# Fibre-Optic-Interface_main.net
KiCad netlist of a schematic drawn in Altium Designer
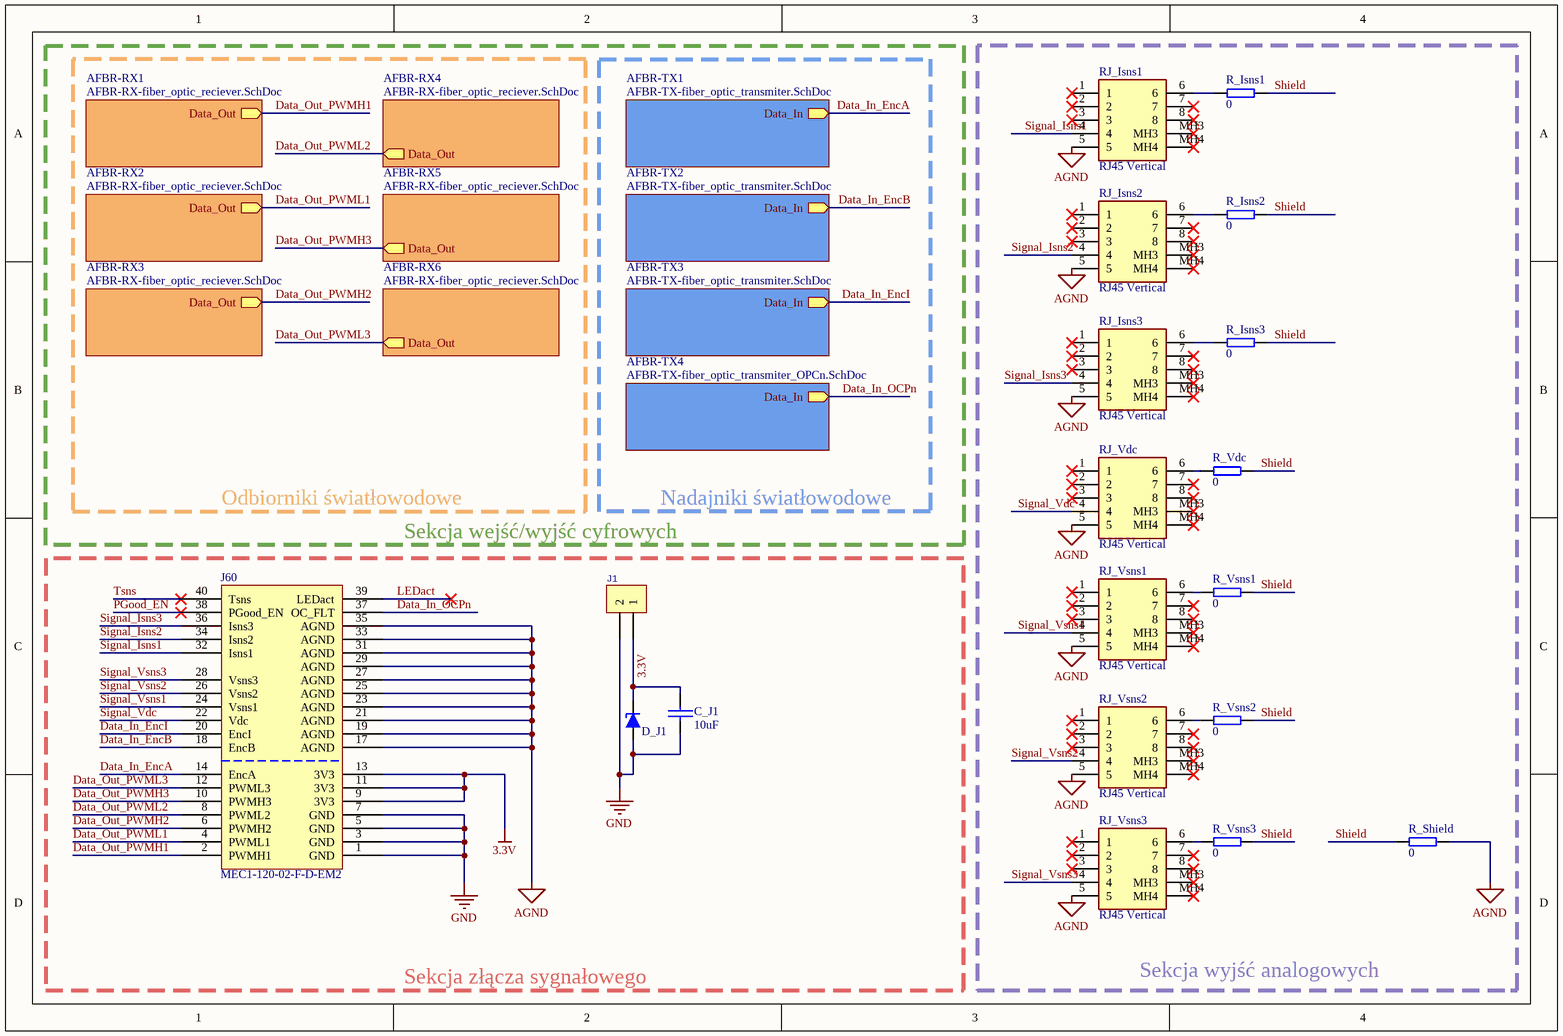
[diagram p0: Fibre-Optic-Interface_main.SchDoc]

(export (version "E")
  (design (tool "Eeschema 10.0.6"))
  (components
    (comp (ref "C_J1")
      (value "10uF")
      (footprint "0603C")
      (description "Capacitor")
      (libsource (lib "PCB_OFC") (part "C_1"))
    )
    (comp (ref "D_J1")
      (value "DIODE_ZENER")
      (footprint "Mini MELF - D")
      (libsource (lib "PCB_OFC") (part "DIODE_ZENER"))
    )
    (comp (ref "J1")
      (value "Header_2")
      (footprint "TBG2-3.5MM_H")
      (libsource (lib "others") (part "Header_2"))
    )
    (comp (ref "J60")
      (value "MEC1-120-02-F-D-EM2")
      (footprint "J60_Connector")
      (description "Connector J60")
      (libsource (lib "connectors") (part "Control interface connector"))
    )
    (comp (ref "RJ_Isns1")
      (value "RJ45 Vertical")
      (footprint "CUC-SP-J1ST-S/R4LT")
      (libsource (lib "Project_4_layers") (part "CUC-SP-J1ST-S/R4LT"))
    )
    (comp (ref "RJ_Isns2")
      (value "RJ45 Vertical")
      (footprint "CUC-SP-J1ST-S/R4LT")
      (libsource (lib "Project_4_layers") (part "CUC-SP-J1ST-S/R4LT"))
    )
    (comp (ref "RJ_Isns3")
      (value "RJ45 Vertical")
      (footprint "CUC-SP-J1ST-S/R4LT")
      (libsource (lib "Project_4_layers") (part "CUC-SP-J1ST-S/R4LT"))
    )
    (comp (ref "RJ_Vdc")
      (value "RJ45 Vertical")
      (footprint "CUC-SP-J1ST-S/R4LT")
      (libsource (lib "Project_4_layers") (part "CUC-SP-J1ST-S/R4LT"))
    )
    (comp (ref "RJ_Vsns1")
      (value "RJ45 Vertical")
      (footprint "CUC-SP-J1ST-S/R4LT")
      (libsource (lib "Project_4_layers") (part "CUC-SP-J1ST-S/R4LT"))
    )
    (comp (ref "RJ_Vsns2")
      (value "RJ45 Vertical")
      (footprint "CUC-SP-J1ST-S/R4LT")
      (libsource (lib "Project_4_layers") (part "CUC-SP-J1ST-S/R4LT"))
    )
    (comp (ref "RJ_Vsns3")
      (value "RJ45 Vertical")
      (footprint "CUC-SP-J1ST-S/R4LT")
      (libsource (lib "Project_4_layers") (part "CUC-SP-J1ST-S/R4LT"))
    )
    (comp (ref "R_Isns1") (value "0") (footprint "0603R") (libsource (lib "passive_elements") (part "R")))
    (comp (ref "R_Isns2") (value "0") (footprint "0603R") (libsource (lib "passive_elements") (part "R")))
    (comp (ref "R_Isns3") (value "0") (footprint "0603R") (libsource (lib "passive_elements") (part "R")))
    (comp (ref "R_Shield") (value "0") (footprint "0603R") (libsource (lib "passive_elements") (part "R")))
    (comp (ref "R_Vdc") (value "0") (footprint "0603R") (libsource (lib "passive_elements") (part "R")))
    (comp (ref "R_Vsns1") (value "0") (footprint "0603R") (libsource (lib "passive_elements") (part "R")))
    (comp (ref "R_Vsns2") (value "0") (footprint "0603R") (libsource (lib "passive_elements") (part "R")))
    (comp (ref "R_Vsns3") (value "0") (footprint "0603R") (libsource (lib "passive_elements") (part "R")))
  )
  (nets
    (net (code "1") (name "/Data_In_EncA") (class "Default")
      (node (ref "J60") (pin "14") (pinfunction "EncA_14") (pintype "passive"))
    )
    (net (code "2") (name "/Data_In_EncB") (class "Default")
      (node (ref "J60") (pin "18") (pinfunction "EncB_18") (pintype "passive"))
    )
    (net (code "3") (name "/Data_In_EncI") (class "Default")
      (node (ref "J60") (pin "20") (pinfunction "EncI_20") (pintype "passive"))
    )
    (net (code "4") (name "/Data_In_OCPn") (class "Default")
      (node (ref "J60") (pin "37") (pinfunction "OC_FLT_37") (pintype "passive"))
    )
    (net (code "5") (name "/Data_Out_PWMH1") (class "Default")
      (node (ref "J60") (pin "2") (pinfunction "PWMH1_2") (pintype "passive"))
    )
    (net (code "6") (name "/Data_Out_PWMH2") (class "Default")
      (node (ref "J60") (pin "6") (pinfunction "PWMH2_6") (pintype "passive"))
    )
    (net (code "7") (name "/Data_Out_PWMH3") (class "Default")
      (node (ref "J60") (pin "10") (pinfunction "PWMH3_10") (pintype "passive"))
    )
    (net (code "8") (name "/Data_Out_PWML1") (class "Default")
      (node (ref "J60") (pin "4") (pinfunction "PWML1_4") (pintype "passive"))
    )
    (net (code "9") (name "/Data_Out_PWML2") (class "Default")
      (node (ref "J60") (pin "8") (pinfunction "PWML2_8") (pintype "passive"))
    )
    (net (code "10") (name "/Data_Out_PWML3") (class "Default")
      (node (ref "J60") (pin "12") (pinfunction "PWML3_12") (pintype "passive"))
    )
    (net (code "11") (name "/LEDact") (class "Default")
      (node (ref "J60") (pin "39") (pinfunction "LEDact_39") (pintype "passive+no_connect"))
    )
    (net (code "12") (name "/PGood_EN") (class "Default")
      (node (ref "J60") (pin "38") (pinfunction "PGood_EN_38") (pintype "passive+no_connect"))
    )
    (net (code "13") (name "/Shield") (class "Default")
      (node (ref "R_Isns1") (pin "2") (pinfunction "2_2") (pintype "passive"))
      (node (ref "R_Isns2") (pin "2") (pinfunction "2_2") (pintype "passive"))
      (node (ref "R_Isns3") (pin "2") (pinfunction "2_2") (pintype "passive"))
      (node (ref "R_Shield") (pin "1") (pinfunction "1_1") (pintype "passive"))
      (node (ref "R_Vdc") (pin "2") (pinfunction "2_2") (pintype "passive"))
      (node (ref "R_Vsns1") (pin "2") (pinfunction "2_2") (pintype "passive"))
      (node (ref "R_Vsns2") (pin "2") (pinfunction "2_2") (pintype "passive"))
      (node (ref "R_Vsns3") (pin "2") (pinfunction "2_2") (pintype "passive"))
    )
    (net (code "14") (name "/Signal_Isns1") (class "Default")
      (node (ref "J60") (pin "32") (pinfunction "Isns1_32") (pintype "passive"))
      (node (ref "RJ_Isns1") (pin "4") (pinfunction "4_4") (pintype "passive"))
    )
    (net (code "15") (name "/Signal_Isns2") (class "Default")
      (node (ref "J60") (pin "34") (pinfunction "Isns2_34") (pintype "passive"))
      (node (ref "RJ_Isns2") (pin "4") (pinfunction "4_4") (pintype "passive"))
    )
    (net (code "16") (name "/Signal_Isns3") (class "Default")
      (node (ref "J60") (pin "36") (pinfunction "Isns3_36") (pintype "passive"))
      (node (ref "RJ_Isns3") (pin "4") (pinfunction "4_4") (pintype "passive"))
    )
    (net (code "17") (name "/Signal_Vdc") (class "Default")
      (node (ref "J60") (pin "22") (pinfunction "Vdc_22") (pintype "passive"))
      (node (ref "RJ_Vdc") (pin "4") (pinfunction "4_4") (pintype "passive"))
    )
    (net (code "18") (name "/Signal_Vsns1") (class "Default")
      (node (ref "J60") (pin "24") (pinfunction "Vsns1_24") (pintype "passive"))
      (node (ref "RJ_Vsns1") (pin "4") (pinfunction "4_4") (pintype "passive"))
    )
    (net (code "19") (name "/Signal_Vsns2") (class "Default")
      (node (ref "J60") (pin "26") (pinfunction "Vsns2_26") (pintype "passive"))
      (node (ref "RJ_Vsns2") (pin "4") (pinfunction "4_4") (pintype "passive"))
    )
    (net (code "20") (name "/Signal_Vsns3") (class "Default")
      (node (ref "J60") (pin "28") (pinfunction "Vsns3_28") (pintype "passive"))
      (node (ref "RJ_Vsns3") (pin "4") (pinfunction "4_4") (pintype "passive"))
    )
    (net (code "21") (name "/Tsns") (class "Default")
      (node (ref "J60") (pin "40") (pinfunction "Tsns_40") (pintype "passive+no_connect"))
    )
    (net (code "22") (name "3.3V") (class "Default")
      (node (ref "C_J1") (pin "1") (pinfunction "1_1") (pintype "passive"))
      (node (ref "D_J1") (pin "K") (pinfunction "K_K") (pintype "passive"))
      (node (ref "J1") (pin "1") (pinfunction "1_1") (pintype "passive"))
      (node (ref "J60") (pin "11") (pinfunction "3V3_11") (pintype "passive"))
      (node (ref "J60") (pin "13") (pinfunction "3V3_13") (pintype "passive"))
      (node (ref "J60") (pin "9") (pinfunction "3V3_9") (pintype "passive"))
    )
    (net (code "23") (name "AGND") (class "Default")
      (node (ref "J60") (pin "17") (pinfunction "AGND_17") (pintype "passive"))
      (node (ref "J60") (pin "19") (pinfunction "AGND_19") (pintype "passive"))
      (node (ref "J60") (pin "21") (pinfunction "AGND_21") (pintype "passive"))
      (node (ref "J60") (pin "23") (pinfunction "AGND_23") (pintype "passive"))
      (node (ref "J60") (pin "25") (pinfunction "AGND_25") (pintype "passive"))
      (node (ref "J60") (pin "27") (pinfunction "AGND_27") (pintype "passive"))
      (node (ref "J60") (pin "29") (pinfunction "AGND_29") (pintype "passive"))
      (node (ref "J60") (pin "31") (pinfunction "AGND_31") (pintype "passive"))
      (node (ref "J60") (pin "33") (pinfunction "AGND_33") (pintype "passive"))
      (node (ref "J60") (pin "35") (pinfunction "AGND_35") (pintype "passive"))
      (node (ref "RJ_Isns1") (pin "5") (pinfunction "5_5") (pintype "passive"))
      (node (ref "RJ_Isns2") (pin "5") (pinfunction "5_5") (pintype "passive"))
      (node (ref "RJ_Isns3") (pin "5") (pinfunction "5_5") (pintype "passive"))
      (node (ref "RJ_Vdc") (pin "5") (pinfunction "5_5") (pintype "passive"))
      (node (ref "RJ_Vsns1") (pin "5") (pinfunction "5_5") (pintype "passive"))
      (node (ref "RJ_Vsns2") (pin "5") (pinfunction "5_5") (pintype "passive"))
      (node (ref "RJ_Vsns3") (pin "5") (pinfunction "5_5") (pintype "passive"))
      (node (ref "R_Shield") (pin "2") (pinfunction "2_2") (pintype "passive"))
    )
    (net (code "24") (name "GND") (class "Default")
      (node (ref "C_J1") (pin "2") (pinfunction "2_2") (pintype "passive"))
      (node (ref "D_J1") (pin "A") (pinfunction "A_A") (pintype "passive"))
      (node (ref "J1") (pin "2") (pinfunction "2_2") (pintype "passive"))
      (node (ref "J60") (pin "1") (pinfunction "GND_1") (pintype "passive"))
      (node (ref "J60") (pin "3") (pinfunction "GND_3") (pintype "passive"))
      (node (ref "J60") (pin "5") (pinfunction "GND_5") (pintype "passive"))
      (node (ref "J60") (pin "7") (pinfunction "GND_7") (pintype "passive"))
    )
    (net (code "25") (name "Net-(RJ_Isns1-Pad6)") (class "Default")
      (node (ref "RJ_Isns1") (pin "6") (pinfunction "6_6") (pintype "passive"))
      (node (ref "R_Isns1") (pin "1") (pinfunction "1_1") (pintype "passive"))
    )
    (net (code "26") (name "Net-(RJ_Isns2-Pad6)") (class "Default")
      (node (ref "RJ_Isns2") (pin "6") (pinfunction "6_6") (pintype "passive"))
      (node (ref "R_Isns2") (pin "1") (pinfunction "1_1") (pintype "passive"))
    )
    (net (code "27") (name "Net-(RJ_Isns3-Pad6)") (class "Default")
      (node (ref "RJ_Isns3") (pin "6") (pinfunction "6_6") (pintype "passive"))
      (node (ref "R_Isns3") (pin "1") (pinfunction "1_1") (pintype "passive"))
    )
    (net (code "28") (name "Net-(RJ_Vdc-Pad6)") (class "Default")
      (node (ref "RJ_Vdc") (pin "6") (pinfunction "6_6") (pintype "passive"))
      (node (ref "R_Vdc") (pin "1") (pinfunction "1_1") (pintype "passive"))
    )
    (net (code "29") (name "Net-(RJ_Vsns1-Pad6)") (class "Default")
      (node (ref "RJ_Vsns1") (pin "6") (pinfunction "6_6") (pintype "passive"))
      (node (ref "R_Vsns1") (pin "1") (pinfunction "1_1") (pintype "passive"))
    )
    (net (code "30") (name "Net-(RJ_Vsns2-Pad6)") (class "Default")
      (node (ref "RJ_Vsns2") (pin "6") (pinfunction "6_6") (pintype "passive"))
      (node (ref "R_Vsns2") (pin "1") (pinfunction "1_1") (pintype "passive"))
    )
    (net (code "31") (name "Net-(RJ_Vsns3-Pad6)") (class "Default")
      (node (ref "RJ_Vsns3") (pin "6") (pinfunction "6_6") (pintype "passive"))
      (node (ref "R_Vsns3") (pin "1") (pinfunction "1_1") (pintype "passive"))
    )
    (net (code "32") (name "unconnected-(RJ_Isns1-Pad1)") (class "Default")
      (node (ref "RJ_Isns1") (pin "1") (pinfunction "1_1") (pintype "passive+no_connect"))
    )
    (net (code "33") (name "unconnected-(RJ_Isns1-Pad2)") (class "Default")
      (node (ref "RJ_Isns1") (pin "2") (pinfunction "2_2") (pintype "passive+no_connect"))
    )
    (net (code "34") (name "unconnected-(RJ_Isns1-Pad3)") (class "Default")
      (node (ref "RJ_Isns1") (pin "3") (pinfunction "3_3") (pintype "passive+no_connect"))
    )
    (net (code "35") (name "unconnected-(RJ_Isns1-Pad7)") (class "Default")
      (node (ref "RJ_Isns1") (pin "7") (pinfunction "7_7") (pintype "passive+no_connect"))
    )
    (net (code "36") (name "unconnected-(RJ_Isns1-Pad8)") (class "Default")
      (node (ref "RJ_Isns1") (pin "8") (pinfunction "8_8") (pintype "passive+no_connect"))
    )
    (net (code "37") (name "unconnected-(RJ_Isns1-PadMH3)") (class "Default")
      (node (ref "RJ_Isns1") (pin "MH3") (pinfunction "MH3_MH3") (pintype "passive+no_connect"))
    )
    (net (code "38") (name "unconnected-(RJ_Isns1-PadMH4)") (class "Default")
      (node (ref "RJ_Isns1") (pin "MH4") (pinfunction "MH4_MH4") (pintype "passive+no_connect"))
    )
    (net (code "39") (name "unconnected-(RJ_Isns2-Pad1)") (class "Default")
      (node (ref "RJ_Isns2") (pin "1") (pinfunction "1_1") (pintype "passive+no_connect"))
    )
    (net (code "40") (name "unconnected-(RJ_Isns2-Pad2)") (class "Default")
      (node (ref "RJ_Isns2") (pin "2") (pinfunction "2_2") (pintype "passive+no_connect"))
    )
    (net (code "41") (name "unconnected-(RJ_Isns2-Pad3)") (class "Default")
      (node (ref "RJ_Isns2") (pin "3") (pinfunction "3_3") (pintype "passive+no_connect"))
    )
    (net (code "42") (name "unconnected-(RJ_Isns2-Pad7)") (class "Default")
      (node (ref "RJ_Isns2") (pin "7") (pinfunction "7_7") (pintype "passive+no_connect"))
    )
    (net (code "43") (name "unconnected-(RJ_Isns2-Pad8)") (class "Default")
      (node (ref "RJ_Isns2") (pin "8") (pinfunction "8_8") (pintype "passive+no_connect"))
    )
    (net (code "44") (name "unconnected-(RJ_Isns2-PadMH3)") (class "Default")
      (node (ref "RJ_Isns2") (pin "MH3") (pinfunction "MH3_MH3") (pintype "passive+no_connect"))
    )
    (net (code "45") (name "unconnected-(RJ_Isns2-PadMH4)") (class "Default")
      (node (ref "RJ_Isns2") (pin "MH4") (pinfunction "MH4_MH4") (pintype "passive+no_connect"))
    )
    (net (code "46") (name "unconnected-(RJ_Isns3-Pad1)") (class "Default")
      (node (ref "RJ_Isns3") (pin "1") (pinfunction "1_1") (pintype "passive+no_connect"))
    )
    (net (code "47") (name "unconnected-(RJ_Isns3-Pad2)") (class "Default")
      (node (ref "RJ_Isns3") (pin "2") (pinfunction "2_2") (pintype "passive+no_connect"))
    )
    (net (code "48") (name "unconnected-(RJ_Isns3-Pad3)") (class "Default")
      (node (ref "RJ_Isns3") (pin "3") (pinfunction "3_3") (pintype "passive+no_connect"))
    )
    (net (code "49") (name "unconnected-(RJ_Isns3-Pad7)") (class "Default")
      (node (ref "RJ_Isns3") (pin "7") (pinfunction "7_7") (pintype "passive+no_connect"))
    )
    (net (code "50") (name "unconnected-(RJ_Isns3-Pad8)") (class "Default")
      (node (ref "RJ_Isns3") (pin "8") (pinfunction "8_8") (pintype "passive+no_connect"))
    )
    (net (code "51") (name "unconnected-(RJ_Isns3-PadMH3)") (class "Default")
      (node (ref "RJ_Isns3") (pin "MH3") (pinfunction "MH3_MH3") (pintype "passive+no_connect"))
    )
    (net (code "52") (name "unconnected-(RJ_Isns3-PadMH4)") (class "Default")
      (node (ref "RJ_Isns3") (pin "MH4") (pinfunction "MH4_MH4") (pintype "passive+no_connect"))
    )
    (net (code "53") (name "unconnected-(RJ_Vdc-Pad1)") (class "Default")
      (node (ref "RJ_Vdc") (pin "1") (pinfunction "1_1") (pintype "passive+no_connect"))
    )
    (net (code "54") (name "unconnected-(RJ_Vdc-Pad2)") (class "Default")
      (node (ref "RJ_Vdc") (pin "2") (pinfunction "2_2") (pintype "passive+no_connect"))
    )
    (net (code "55") (name "unconnected-(RJ_Vdc-Pad3)") (class "Default")
      (node (ref "RJ_Vdc") (pin "3") (pinfunction "3_3") (pintype "passive+no_connect"))
    )
    (net (code "56") (name "unconnected-(RJ_Vdc-Pad7)") (class "Default")
      (node (ref "RJ_Vdc") (pin "7") (pinfunction "7_7") (pintype "passive+no_connect"))
    )
    (net (code "57") (name "unconnected-(RJ_Vdc-Pad8)") (class "Default")
      (node (ref "RJ_Vdc") (pin "8") (pinfunction "8_8") (pintype "passive+no_connect"))
    )
    (net (code "58") (name "unconnected-(RJ_Vdc-PadMH3)") (class "Default")
      (node (ref "RJ_Vdc") (pin "MH3") (pinfunction "MH3_MH3") (pintype "passive+no_connect"))
    )
    (net (code "59") (name "unconnected-(RJ_Vdc-PadMH4)") (class "Default")
      (node (ref "RJ_Vdc") (pin "MH4") (pinfunction "MH4_MH4") (pintype "passive+no_connect"))
    )
    (net (code "60") (name "unconnected-(RJ_Vsns1-Pad1)") (class "Default")
      (node (ref "RJ_Vsns1") (pin "1") (pinfunction "1_1") (pintype "passive+no_connect"))
    )
    (net (code "61") (name "unconnected-(RJ_Vsns1-Pad2)") (class "Default")
      (node (ref "RJ_Vsns1") (pin "2") (pinfunction "2_2") (pintype "passive+no_connect"))
    )
    (net (code "62") (name "unconnected-(RJ_Vsns1-Pad3)") (class "Default")
      (node (ref "RJ_Vsns1") (pin "3") (pinfunction "3_3") (pintype "passive+no_connect"))
    )
    (net (code "63") (name "unconnected-(RJ_Vsns1-Pad7)") (class "Default")
      (node (ref "RJ_Vsns1") (pin "7") (pinfunction "7_7") (pintype "passive+no_connect"))
    )
    (net (code "64") (name "unconnected-(RJ_Vsns1-Pad8)") (class "Default")
      (node (ref "RJ_Vsns1") (pin "8") (pinfunction "8_8") (pintype "passive+no_connect"))
    )
    (net (code "65") (name "unconnected-(RJ_Vsns1-PadMH3)") (class "Default")
      (node (ref "RJ_Vsns1") (pin "MH3") (pinfunction "MH3_MH3") (pintype "passive+no_connect"))
    )
    (net (code "66") (name "unconnected-(RJ_Vsns1-PadMH4)") (class "Default")
      (node (ref "RJ_Vsns1") (pin "MH4") (pinfunction "MH4_MH4") (pintype "passive+no_connect"))
    )
    (net (code "67") (name "unconnected-(RJ_Vsns2-Pad1)") (class "Default")
      (node (ref "RJ_Vsns2") (pin "1") (pinfunction "1_1") (pintype "passive+no_connect"))
    )
    (net (code "68") (name "unconnected-(RJ_Vsns2-Pad2)") (class "Default")
      (node (ref "RJ_Vsns2") (pin "2") (pinfunction "2_2") (pintype "passive+no_connect"))
    )
    (net (code "69") (name "unconnected-(RJ_Vsns2-Pad3)") (class "Default")
      (node (ref "RJ_Vsns2") (pin "3") (pinfunction "3_3") (pintype "passive+no_connect"))
    )
    (net (code "70") (name "unconnected-(RJ_Vsns2-Pad7)") (class "Default")
      (node (ref "RJ_Vsns2") (pin "7") (pinfunction "7_7") (pintype "passive+no_connect"))
    )
    (net (code "71") (name "unconnected-(RJ_Vsns2-Pad8)") (class "Default")
      (node (ref "RJ_Vsns2") (pin "8") (pinfunction "8_8") (pintype "passive+no_connect"))
    )
    (net (code "72") (name "unconnected-(RJ_Vsns2-PadMH3)") (class "Default")
      (node (ref "RJ_Vsns2") (pin "MH3") (pinfunction "MH3_MH3") (pintype "passive+no_connect"))
    )
    (net (code "73") (name "unconnected-(RJ_Vsns2-PadMH4)") (class "Default")
      (node (ref "RJ_Vsns2") (pin "MH4") (pinfunction "MH4_MH4") (pintype "passive+no_connect"))
    )
    (net (code "74") (name "unconnected-(RJ_Vsns3-Pad1)") (class "Default")
      (node (ref "RJ_Vsns3") (pin "1") (pinfunction "1_1") (pintype "passive+no_connect"))
    )
    (net (code "75") (name "unconnected-(RJ_Vsns3-Pad2)") (class "Default")
      (node (ref "RJ_Vsns3") (pin "2") (pinfunction "2_2") (pintype "passive+no_connect"))
    )
    (net (code "76") (name "unconnected-(RJ_Vsns3-Pad3)") (class "Default")
      (node (ref "RJ_Vsns3") (pin "3") (pinfunction "3_3") (pintype "passive+no_connect"))
    )
    (net (code "77") (name "unconnected-(RJ_Vsns3-Pad7)") (class "Default")
      (node (ref "RJ_Vsns3") (pin "7") (pinfunction "7_7") (pintype "passive+no_connect"))
    )
    (net (code "78") (name "unconnected-(RJ_Vsns3-Pad8)") (class "Default")
      (node (ref "RJ_Vsns3") (pin "8") (pinfunction "8_8") (pintype "passive+no_connect"))
    )
    (net (code "79") (name "unconnected-(RJ_Vsns3-PadMH3)") (class "Default")
      (node (ref "RJ_Vsns3") (pin "MH3") (pinfunction "MH3_MH3") (pintype "passive+no_connect"))
    )
    (net (code "80") (name "unconnected-(RJ_Vsns3-PadMH4)") (class "Default")
      (node (ref "RJ_Vsns3") (pin "MH4") (pinfunction "MH4_MH4") (pintype "passive+no_connect"))
    )
  )
)
